# stmschematic.net
KiCad netlist of a schematic drawn in Altium Designer
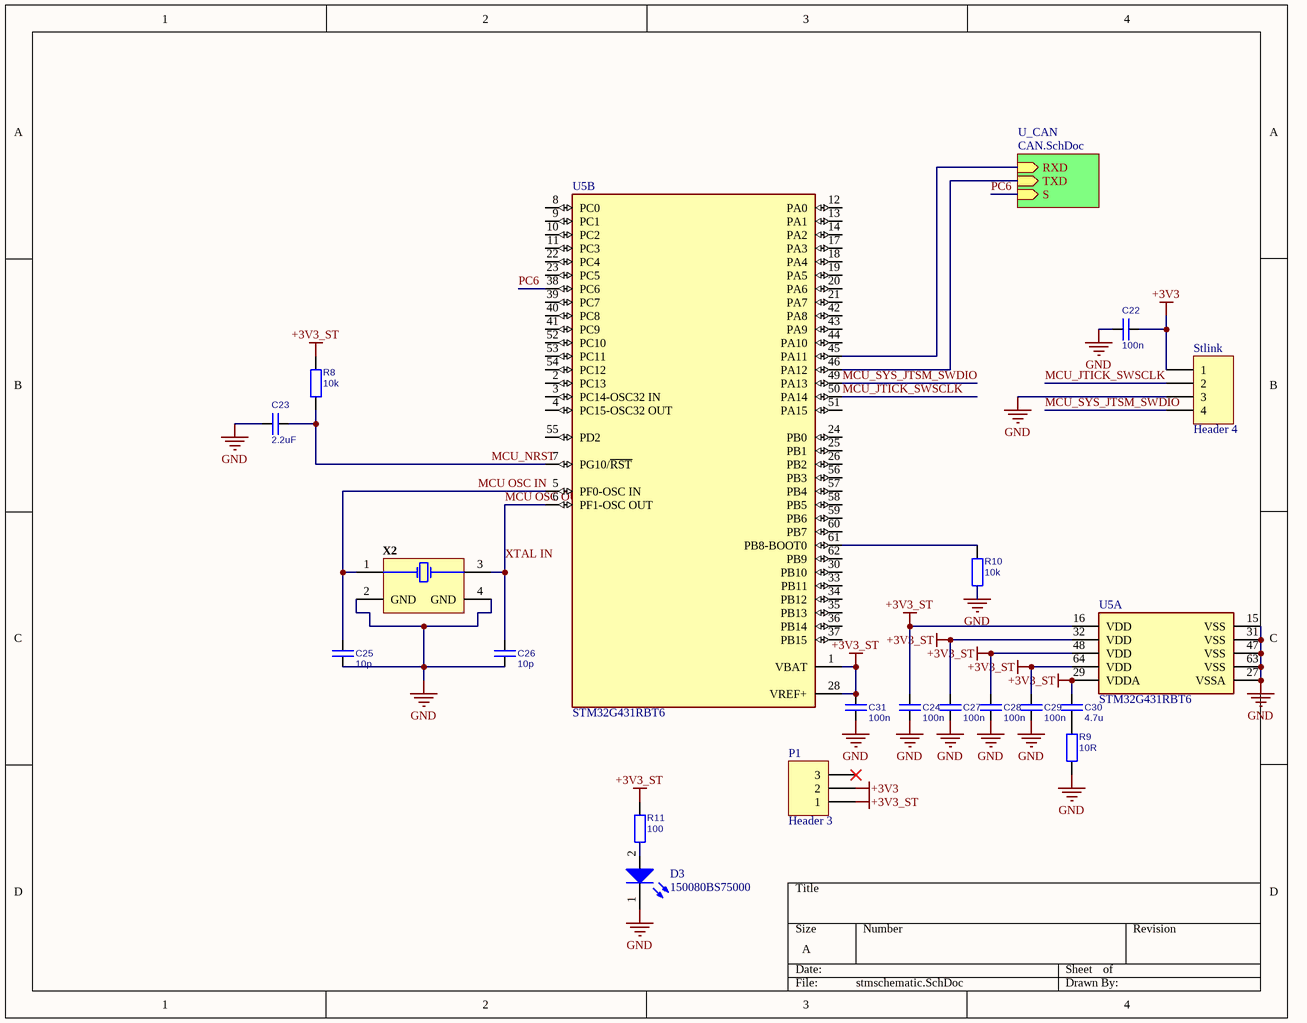
[diagram p0: stmschematic.SchDoc]

(export (version "E")
  (design (tool "Eeschema 10.0.6"))
  (components
    (comp (ref "C22")
      (value "100n")
      (footprint "C0603")
      (description "Capacitor")
      (libsource (lib "General") (part "C"))
    )
    (comp (ref "C23")
      (value "2.2uF")
      (footprint "C0603")
      (description "Capacitor")
      (libsource (lib "General") (part "C"))
    )
    (comp (ref "C24")
      (value "100n")
      (footprint "C0603")
      (description "Capacitor")
      (libsource (lib "General") (part "C"))
    )
    (comp (ref "C25")
      (value "10p")
      (footprint "C0603")
      (description "Capacitor")
      (libsource (lib "General") (part "C"))
    )
    (comp (ref "C26")
      (value "10p")
      (footprint "C0603")
      (description "Capacitor")
      (libsource (lib "General") (part "C"))
    )
    (comp (ref "C27")
      (value "100n")
      (footprint "C0603")
      (description "Capacitor")
      (libsource (lib "General") (part "C"))
    )
    (comp (ref "C28")
      (value "100n")
      (footprint "C0603")
      (description "Capacitor")
      (libsource (lib "General") (part "C"))
    )
    (comp (ref "C29")
      (value "100n")
      (footprint "C0603")
      (description "Capacitor")
      (libsource (lib "General") (part "C"))
    )
    (comp (ref "C30")
      (value "4.7u")
      (footprint "C0603")
      (description "Capacitor")
      (libsource (lib "General") (part "C"))
    )
    (comp (ref "C31")
      (value "100n")
      (footprint "C0603")
      (description "Capacitor")
      (libsource (lib "General") (part "C"))
    )
    (comp (ref "D3")
      (value "150080BS75000")
      (footprint "WL-SMCW_0805_150080xx75000")
      (libsource (lib "Altium Content Vault") (part "LED_Blue_2A-1K"))
    )
    (comp (ref "P1")
      (value "Header 3")
      (footprint "HDR1X3")
      (description "Header, 3-Pin")
      (fields (field (name "PUBLISHER") "Altium Limited"))
      (libsource (lib "Miscellaneous Connectors") (part "Header 3"))
    )
    (comp (ref "R8")
      (value "10k")
      (footprint "R0603")
      (description "R")
      (libsource (lib "General") (part "R"))
    )
    (comp (ref "R9")
      (value "10R")
      (footprint "R0603")
      (description "R")
      (libsource (lib "General") (part "R"))
    )
    (comp (ref "R10")
      (value "10k")
      (footprint "R0603")
      (description "R")
      (libsource (lib "General") (part "R"))
    )
    (comp (ref "R11")
      (value "100")
      (footprint "R0603")
      (description "R")
      (libsource (lib "General") (part "R"))
    )
    (comp (ref "Stlink")
      (value "Header 4")
      (footprint "HDR1X4")
      (description "Header, 4-Pin")
      (fields (field (name "PUBLISHER") "Altium Limited"))
      (libsource (lib "Miscellaneous Connectors") (part "Header 4"))
    )
    (comp (ref "U5")
      (value "STM32G431RBT6")
      (footprint "FP-LQFP64-5W-MFG")
      (description "IC MCU 32BIT 128KB FLASH 64LQFP")
      (libsource (lib "") (part "d6c5d394e20af6b50f80b096c052b1c_1"))
    )
    (comp (ref "X2")
      (value "TSX-3225 24.0000MF15X-AC3")
      (footprint "EPSON-TSX-3225_V")
      (description "MHz Range Crystal, 24 MHz, -40 to 85 degC, 4-Pin SMD, RoHS, Tape and Reel")
      (fields (field (name "TOLERANCE") "10PPM") (field (name "MANUFACTURER") "Epson"))
      (libsource (lib "Altium Content Vault") (part "XTAL-1-3-4"))
    )
  )
  (nets
    (net (code "1") (name "+3V3") (class "Default")
      (node (ref "C22") (pin "2") (pinfunction "2_2") (pintype "passive"))
      (node (ref "P1") (pin "2") (pinfunction "2_2") (pintype "passive"))
      (node (ref "Stlink") (pin "1") (pinfunction "1_1") (pintype "passive"))
    )
    (net (code "2") (name "+3V3_ST") (class "Default")
      (node (ref "C24") (pin "1") (pinfunction "1_1") (pintype "passive"))
      (node (ref "C27") (pin "1") (pinfunction "1_1") (pintype "passive"))
      (node (ref "C28") (pin "1") (pinfunction "1_1") (pintype "passive"))
      (node (ref "C29") (pin "1") (pinfunction "1_1") (pintype "passive"))
      (node (ref "C30") (pin "1") (pinfunction "1_1") (pintype "passive"))
      (node (ref "C31") (pin "1") (pinfunction "1_1") (pintype "passive"))
      (node (ref "P1") (pin "1") (pinfunction "1_1") (pintype "passive"))
      (node (ref "R11") (pin "2") (pintype "passive"))
      (node (ref "R8") (pin "1") (pintype "passive"))
      (node (ref "U5") (pin "1") (pinfunction "VBAT_1") (pintype "power_in"))
      (node (ref "U5") (pin "16") (pinfunction "VDD_16") (pintype "power_in"))
      (node (ref "U5") (pin "28") (pinfunction "VREF+_28") (pintype "power_in"))
      (node (ref "U5") (pin "29") (pinfunction "VDDA_29") (pintype "power_in"))
      (node (ref "U5") (pin "32") (pinfunction "VDD_32") (pintype "power_in"))
      (node (ref "U5") (pin "48") (pinfunction "VDD_48") (pintype "power_in"))
      (node (ref "U5") (pin "64") (pinfunction "VDD_64") (pintype "power_in"))
    )
    (net (code "3") (name "/MCU OSC IN") (class "Default")
      (node (ref "C25") (pin "1") (pinfunction "1_1") (pintype "passive"))
      (node (ref "U5") (pin "5") (pinfunction "PF0-OSC_IN_5") (pintype "bidirectional"))
      (node (ref "X2") (pin "1") (pinfunction "X1_1") (pintype "passive"))
    )
    (net (code "4") (name "/MCU OSC OUT") (class "Default")
      (node (ref "C26") (pin "1") (pinfunction "1_1") (pintype "passive"))
      (node (ref "U5") (pin "6") (pinfunction "PF1-OSC_OUT_6") (pintype "bidirectional"))
      (node (ref "X2") (pin "3") (pinfunction "X2_3") (pintype "passive"))
    )
    (net (code "5") (name "/MCU_JTICK_SWSCLK") (class "Default")
      (node (ref "Stlink") (pin "2") (pinfunction "2_2") (pintype "passive"))
      (node (ref "U5") (pin "50") (pinfunction "PA14_50") (pintype "bidirectional"))
    )
    (net (code "6") (name "/MCU_NRST") (class "Default")
      (node (ref "C23") (pin "2") (pinfunction "2_2") (pintype "passive"))
      (node (ref "R8") (pin "2") (pintype "passive"))
      (node (ref "U5") (pin "7") (pinfunction "PG10/~{RST}_7") (pintype "bidirectional"))
    )
    (net (code "7") (name "/MCU_SYS_JTSM_SWDIO") (class "Default")
      (node (ref "Stlink") (pin "4") (pinfunction "4_4") (pintype "passive"))
      (node (ref "U5") (pin "49") (pinfunction "PA13_49") (pintype "bidirectional"))
    )
    (net (code "8") (name "/PC6") (class "Default")
      (node (ref "U5") (pin "38") (pinfunction "PC6_38") (pintype "bidirectional"))
    )
    (net (code "9") (name "/RXD") (class "Default")
      (node (ref "U5") (pin "45") (pinfunction "PA11_45") (pintype "bidirectional"))
    )
    (net (code "10") (name "/TXD") (class "Default")
      (node (ref "U5") (pin "46") (pinfunction "PA12_46") (pintype "bidirectional"))
    )
    (net (code "11") (name "GND") (class "Default")
      (node (ref "C22") (pin "1") (pinfunction "1_1") (pintype "passive"))
      (node (ref "C23") (pin "1") (pinfunction "1_1") (pintype "passive"))
      (node (ref "C24") (pin "2") (pinfunction "2_2") (pintype "passive"))
      (node (ref "C25") (pin "2") (pinfunction "2_2") (pintype "passive"))
      (node (ref "C26") (pin "2") (pinfunction "2_2") (pintype "passive"))
      (node (ref "C27") (pin "2") (pinfunction "2_2") (pintype "passive"))
      (node (ref "C28") (pin "2") (pinfunction "2_2") (pintype "passive"))
      (node (ref "C29") (pin "2") (pinfunction "2_2") (pintype "passive"))
      (node (ref "C31") (pin "2") (pinfunction "2_2") (pintype "passive"))
      (node (ref "D3") (pin "1") (pinfunction "K_1") (pintype "passive"))
      (node (ref "R10") (pin "2") (pintype "passive"))
      (node (ref "R9") (pin "2") (pintype "passive"))
      (node (ref "Stlink") (pin "3") (pinfunction "3_3") (pintype "passive"))
      (node (ref "U5") (pin "15") (pinfunction "VSS_15") (pintype "power_in"))
      (node (ref "U5") (pin "27") (pinfunction "VSSA_27") (pintype "power_in"))
      (node (ref "U5") (pin "31") (pinfunction "VSS_31") (pintype "power_in"))
      (node (ref "U5") (pin "47") (pinfunction "VSS_47") (pintype "power_in"))
      (node (ref "U5") (pin "63") (pinfunction "VSS_63") (pintype "power_in"))
      (node (ref "X2") (pin "2") (pinfunction "GND_2") (pintype "power_in"))
      (node (ref "X2") (pin "4") (pinfunction "GND_4") (pintype "power_in"))
    )
    (net (code "12") (name "Net-(C30-Pad2)") (class "Default")
      (node (ref "C30") (pin "2") (pinfunction "2_2") (pintype "passive"))
      (node (ref "R9") (pin "1") (pintype "passive"))
    )
    (net (code "13") (name "Net-(D3-A)") (class "Default")
      (node (ref "D3") (pin "2") (pinfunction "A_2") (pintype "passive"))
      (node (ref "R11") (pin "1") (pintype "passive"))
    )
    (net (code "14") (name "Net-(U5B-PB8-BOOT0)") (class "Default")
      (node (ref "R10") (pin "1") (pintype "passive"))
      (node (ref "U5") (pin "61") (pinfunction "PB8-BOOT0_61") (pintype "bidirectional"))
    )
    (net (code "15") (name "unconnected-(P1-Pad3)") (class "Default")
      (node (ref "P1") (pin "3") (pinfunction "3_3") (pintype "passive+no_connect"))
    )
    (net (code "16") (name "unconnected-(U5B-PA0-Pad12)") (class "Default")
      (node (ref "U5") (pin "12") (pinfunction "PA0_12") (pintype "bidirectional"))
    )
    (net (code "17") (name "unconnected-(U5B-PA1-Pad13)") (class "Default")
      (node (ref "U5") (pin "13") (pinfunction "PA1_13") (pintype "bidirectional"))
    )
    (net (code "18") (name "unconnected-(U5B-PA2-Pad14)") (class "Default")
      (node (ref "U5") (pin "14") (pinfunction "PA2_14") (pintype "bidirectional"))
    )
    (net (code "19") (name "unconnected-(U5B-PA3-Pad17)") (class "Default")
      (node (ref "U5") (pin "17") (pinfunction "PA3_17") (pintype "bidirectional"))
    )
    (net (code "20") (name "unconnected-(U5B-PA4-Pad18)") (class "Default")
      (node (ref "U5") (pin "18") (pinfunction "PA4_18") (pintype "bidirectional"))
    )
    (net (code "21") (name "unconnected-(U5B-PA5-Pad19)") (class "Default")
      (node (ref "U5") (pin "19") (pinfunction "PA5_19") (pintype "bidirectional"))
    )
    (net (code "22") (name "unconnected-(U5B-PA6-Pad20)") (class "Default")
      (node (ref "U5") (pin "20") (pinfunction "PA6_20") (pintype "bidirectional"))
    )
    (net (code "23") (name "unconnected-(U5B-PA7-Pad21)") (class "Default")
      (node (ref "U5") (pin "21") (pinfunction "PA7_21") (pintype "bidirectional"))
    )
    (net (code "24") (name "unconnected-(U5B-PA8-Pad42)") (class "Default")
      (node (ref "U5") (pin "42") (pinfunction "PA8_42") (pintype "bidirectional"))
    )
    (net (code "25") (name "unconnected-(U5B-PA9-Pad43)") (class "Default")
      (node (ref "U5") (pin "43") (pinfunction "PA9_43") (pintype "bidirectional"))
    )
    (net (code "26") (name "unconnected-(U5B-PA10-Pad44)") (class "Default")
      (node (ref "U5") (pin "44") (pinfunction "PA10_44") (pintype "bidirectional"))
    )
    (net (code "27") (name "unconnected-(U5B-PA15-Pad51)") (class "Default")
      (node (ref "U5") (pin "51") (pinfunction "PA15_51") (pintype "bidirectional"))
    )
    (net (code "28") (name "unconnected-(U5B-PB0-Pad24)") (class "Default")
      (node (ref "U5") (pin "24") (pinfunction "PB0_24") (pintype "bidirectional"))
    )
    (net (code "29") (name "unconnected-(U5B-PB1-Pad25)") (class "Default")
      (node (ref "U5") (pin "25") (pinfunction "PB1_25") (pintype "bidirectional"))
    )
    (net (code "30") (name "unconnected-(U5B-PB2-Pad26)") (class "Default")
      (node (ref "U5") (pin "26") (pinfunction "PB2_26") (pintype "bidirectional"))
    )
    (net (code "31") (name "unconnected-(U5B-PB3-Pad56)") (class "Default")
      (node (ref "U5") (pin "56") (pinfunction "PB3_56") (pintype "bidirectional"))
    )
    (net (code "32") (name "unconnected-(U5B-PB4-Pad57)") (class "Default")
      (node (ref "U5") (pin "57") (pinfunction "PB4_57") (pintype "bidirectional"))
    )
    (net (code "33") (name "unconnected-(U5B-PB5-Pad58)") (class "Default")
      (node (ref "U5") (pin "58") (pinfunction "PB5_58") (pintype "bidirectional"))
    )
    (net (code "34") (name "unconnected-(U5B-PB6-Pad59)") (class "Default")
      (node (ref "U5") (pin "59") (pinfunction "PB6_59") (pintype "bidirectional"))
    )
    (net (code "35") (name "unconnected-(U5B-PB7-Pad60)") (class "Default")
      (node (ref "U5") (pin "60") (pinfunction "PB7_60") (pintype "bidirectional"))
    )
    (net (code "36") (name "unconnected-(U5B-PB9-Pad62)") (class "Default")
      (node (ref "U5") (pin "62") (pinfunction "PB9_62") (pintype "bidirectional"))
    )
    (net (code "37") (name "unconnected-(U5B-PB10-Pad30)") (class "Default")
      (node (ref "U5") (pin "30") (pinfunction "PB10_30") (pintype "bidirectional"))
    )
    (net (code "38") (name "unconnected-(U5B-PB11-Pad33)") (class "Default")
      (node (ref "U5") (pin "33") (pinfunction "PB11_33") (pintype "bidirectional"))
    )
    (net (code "39") (name "unconnected-(U5B-PB12-Pad34)") (class "Default")
      (node (ref "U5") (pin "34") (pinfunction "PB12_34") (pintype "bidirectional"))
    )
    (net (code "40") (name "unconnected-(U5B-PB13-Pad35)") (class "Default")
      (node (ref "U5") (pin "35") (pinfunction "PB13_35") (pintype "bidirectional"))
    )
    (net (code "41") (name "unconnected-(U5B-PB14-Pad36)") (class "Default")
      (node (ref "U5") (pin "36") (pinfunction "PB14_36") (pintype "bidirectional"))
    )
    (net (code "42") (name "unconnected-(U5B-PB15-Pad37)") (class "Default")
      (node (ref "U5") (pin "37") (pinfunction "PB15_37") (pintype "bidirectional"))
    )
    (net (code "43") (name "unconnected-(U5B-PC0-Pad8)") (class "Default")
      (node (ref "U5") (pin "8") (pinfunction "PC0_8") (pintype "bidirectional"))
    )
    (net (code "44") (name "unconnected-(U5B-PC1-Pad9)") (class "Default")
      (node (ref "U5") (pin "9") (pinfunction "PC1_9") (pintype "bidirectional"))
    )
    (net (code "45") (name "unconnected-(U5B-PC2-Pad10)") (class "Default")
      (node (ref "U5") (pin "10") (pinfunction "PC2_10") (pintype "bidirectional"))
    )
    (net (code "46") (name "unconnected-(U5B-PC3-Pad11)") (class "Default")
      (node (ref "U5") (pin "11") (pinfunction "PC3_11") (pintype "bidirectional"))
    )
    (net (code "47") (name "unconnected-(U5B-PC4-Pad22)") (class "Default")
      (node (ref "U5") (pin "22") (pinfunction "PC4_22") (pintype "bidirectional"))
    )
    (net (code "48") (name "unconnected-(U5B-PC5-Pad23)") (class "Default")
      (node (ref "U5") (pin "23") (pinfunction "PC5_23") (pintype "bidirectional"))
    )
    (net (code "49") (name "unconnected-(U5B-PC7-Pad39)") (class "Default")
      (node (ref "U5") (pin "39") (pinfunction "PC7_39") (pintype "bidirectional"))
    )
    (net (code "50") (name "unconnected-(U5B-PC8-Pad40)") (class "Default")
      (node (ref "U5") (pin "40") (pinfunction "PC8_40") (pintype "bidirectional"))
    )
    (net (code "51") (name "unconnected-(U5B-PC9-Pad41)") (class "Default")
      (node (ref "U5") (pin "41") (pinfunction "PC9_41") (pintype "bidirectional"))
    )
    (net (code "52") (name "unconnected-(U5B-PC10-Pad52)") (class "Default")
      (node (ref "U5") (pin "52") (pinfunction "PC10_52") (pintype "bidirectional"))
    )
    (net (code "53") (name "unconnected-(U5B-PC11-Pad53)") (class "Default")
      (node (ref "U5") (pin "53") (pinfunction "PC11_53") (pintype "bidirectional"))
    )
    (net (code "54") (name "unconnected-(U5B-PC12-Pad54)") (class "Default")
      (node (ref "U5") (pin "54") (pinfunction "PC12_54") (pintype "bidirectional"))
    )
    (net (code "55") (name "unconnected-(U5B-PC13-Pad2)") (class "Default")
      (node (ref "U5") (pin "2") (pinfunction "PC13_2") (pintype "bidirectional"))
    )
    (net (code "56") (name "unconnected-(U5B-PC14-OSC32_IN-Pad3)") (class "Default")
      (node (ref "U5") (pin "3") (pinfunction "PC14-OSC32_IN_3") (pintype "bidirectional"))
    )
    (net (code "57") (name "unconnected-(U5B-PC15-OSC32_OUT-Pad4)") (class "Default")
      (node (ref "U5") (pin "4") (pinfunction "PC15-OSC32_OUT_4") (pintype "bidirectional"))
    )
    (net (code "58") (name "unconnected-(U5B-PD2-Pad55)") (class "Default")
      (node (ref "U5") (pin "55") (pinfunction "PD2_55") (pintype "bidirectional"))
    )
  )
)
